# DAC.net
KiCad netlist of a schematic drawn in Altium Designer
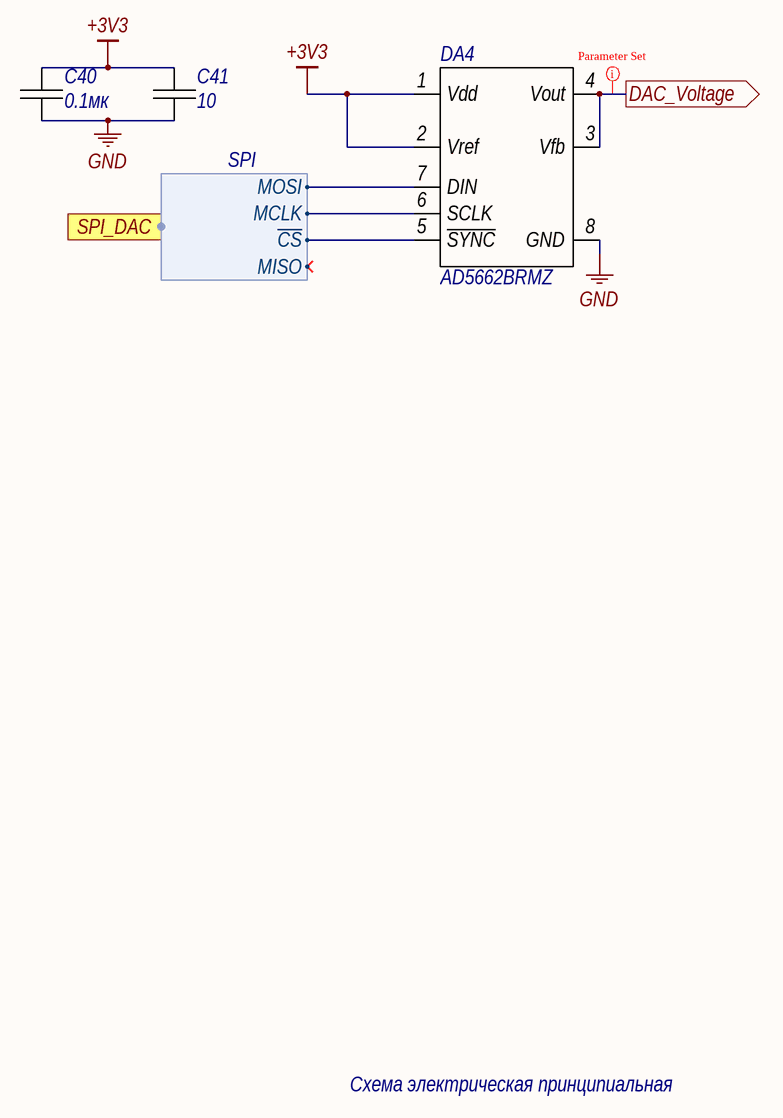
[diagram p0: DAC.SchDoc]

(export (version "E")
  (design (tool "Eeschema 10.0.6"))
  (components
    (comp (ref "C40")
      (value "0.1мк")
      (footprint "CAP0402")
      (fields
        (field (name "MANUFACTURER") "Samsung Electro-Mechanics")
        (field (name "MPN") "CL05B104KB54PNC")
        (field (name "TOLERANCE") "10%")
      )
      (libsource (lib "Library") (part "CAPC"))
    )
    (comp (ref "C41")
      (value "10")
      (footprint "CAP0402")
      (fields
        (field (name "MANUFACTURER") "Samsung Electro-Mechanics")
        (field (name "MPN") "CL05C100JB5NNNC")
        (field (name "VOLTAGE") "50V")
      )
      (libsource (lib "Library") (part "CAPC"))
    )
    (comp (ref "DA4")
      (value "AD5662BRMZ")
      (footprint "TSOP65P490X110-8N")
      (fields
        (field (name "MPN") "AD5662BRMZ")
        (field (name "PART NUMBER") "AD5662")
        (field (name "MANUFACTURER") "Analog Devices")
      )
      (libsource (lib "Library") (part "AD5662"))
    )
  )
  (nets
    (net (code "2") (name "+3V3") (class "Default")
      (node (ref "C40") (pin "2") (pinfunction "2_2") (pintype "passive"))
      (node (ref "C41") (pin "2") (pinfunction "2_2") (pintype "passive"))
      (node (ref "DA4") (pin "1") (pinfunction "Vdd_1") (pintype "passive"))
      (node (ref "DA4") (pin "2") (pinfunction "Vref_2") (pintype "passive"))
    )
    (net (code "3") (name "/DAC_Voltage") (class "Default")
      (node (ref "DA4") (pin "3") (pinfunction "Vfb_3") (pintype "passive"))
      (node (ref "DA4") (pin "4") (pinfunction "Vout_4") (pintype "passive"))
    )
    (net (code "4") (name "/MCLK") (class "Default")
      (node (ref "DA4") (pin "6") (pinfunction "SCLK_6") (pintype "passive"))
    )
    (net (code "5") (name "/MOSI") (class "Default")
      (node (ref "DA4") (pin "7") (pinfunction "DIN_7") (pintype "passive"))
    )
    (net (code "7") (name "/~{CS}") (class "Default")
      (node (ref "DA4") (pin "5") (pinfunction "~{SYNC}_5") (pintype "passive"))
    )
    (net (code "8") (name "GND") (class "Default")
      (node (ref "C40") (pin "1") (pinfunction "1_1") (pintype "passive"))
      (node (ref "C41") (pin "1") (pinfunction "1_1") (pintype "passive"))
      (node (ref "DA4") (pin "8") (pinfunction "GND_8") (pintype "passive"))
    )
  )
)
